# Xadow-GPS-v2.net
KiCad netlist of a schematic drawn in EAGLE
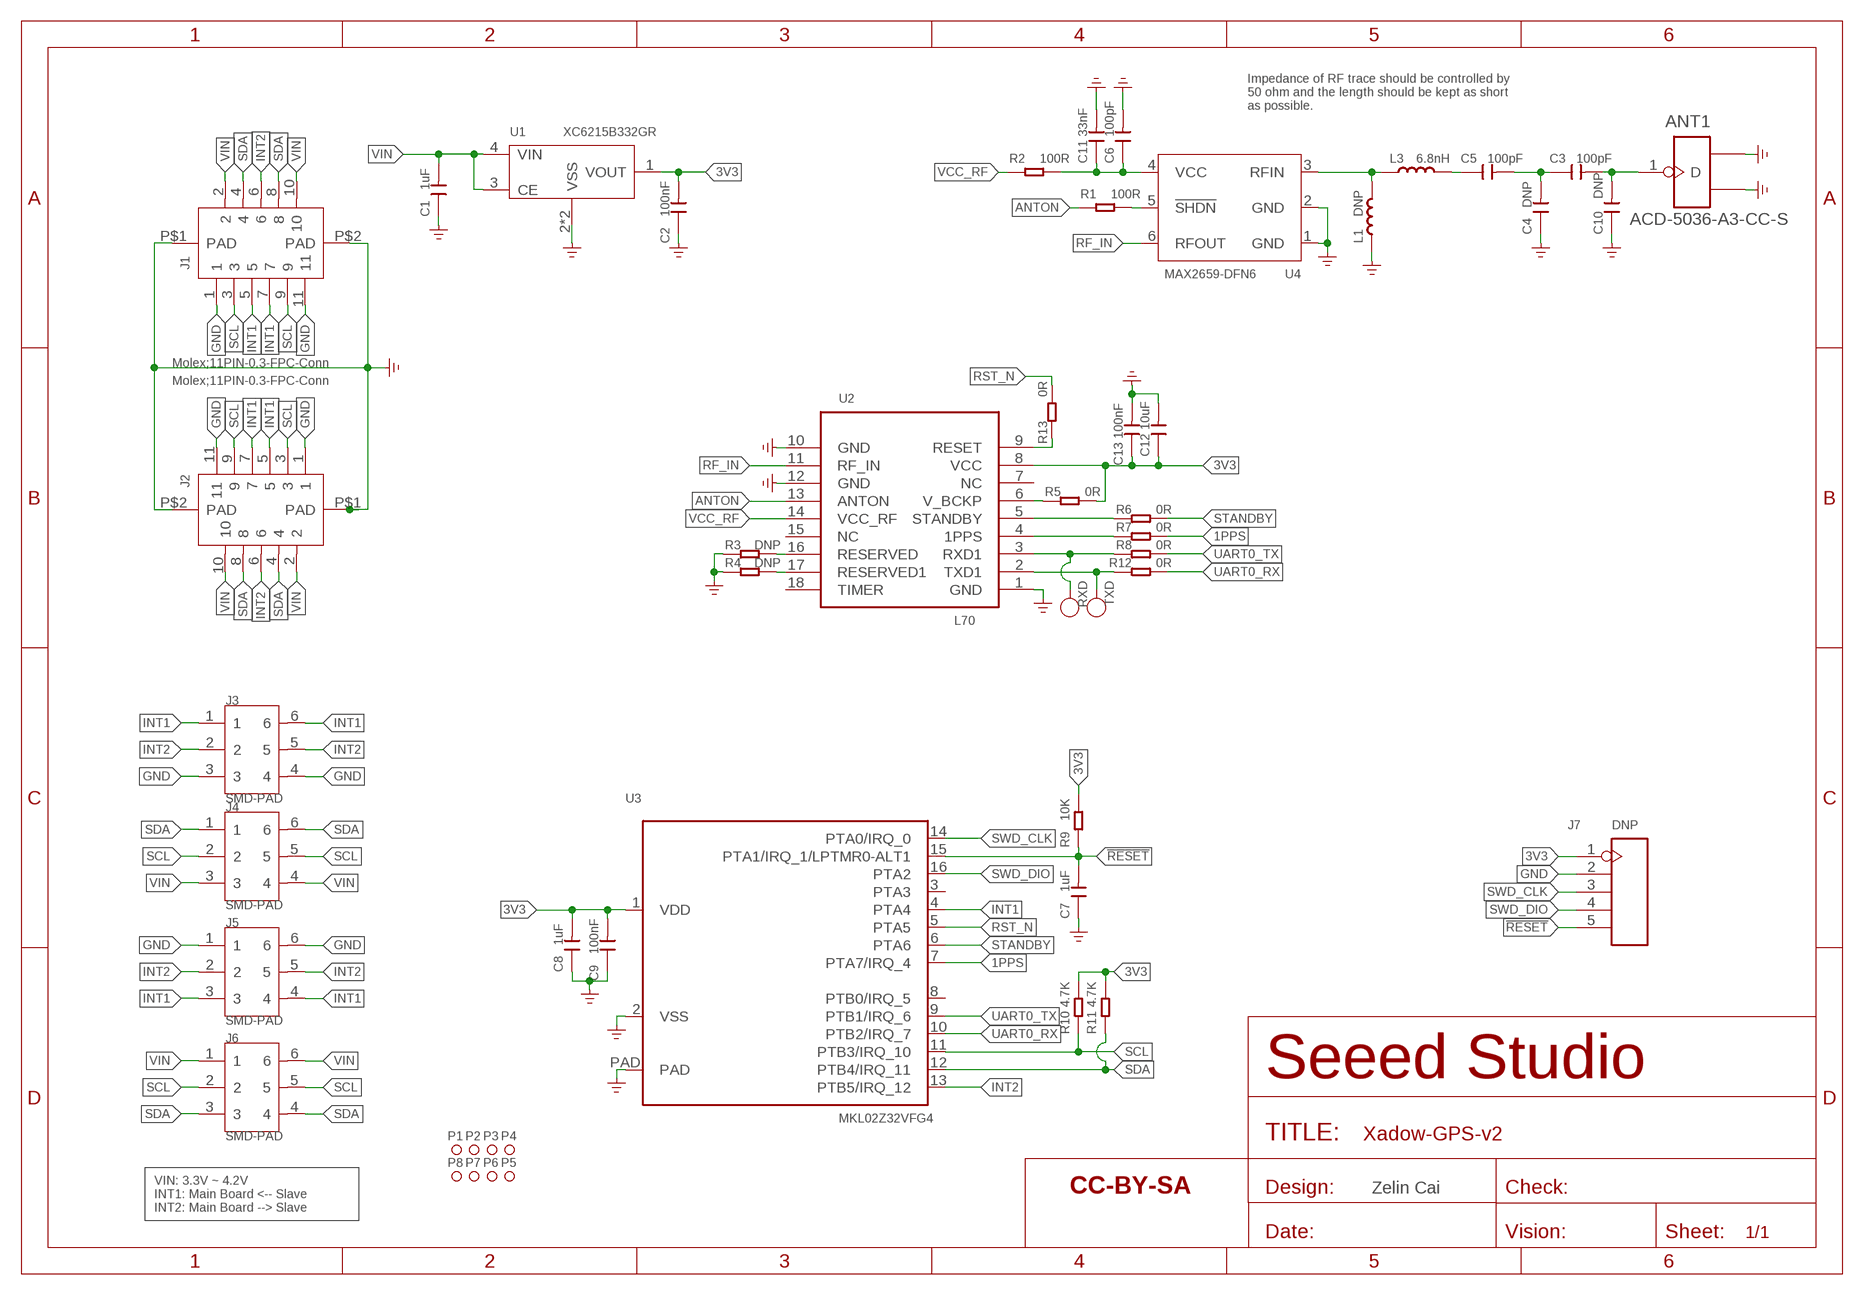
[diagram p0: schematic, sheet 1]

(export (version "E")
  (design (tool "Eeschema 10.0.6"))
  (components
    (comp (ref "ANT1")
      (value "ACD-5036-A3-CC-S")
      (footprint "eagle-import:ANT3-SMD-5.2X3.7X0.7MM")
      (libsource (lib "eagle-import") (part "ANTENNA-ACD5036"))
    )
    (comp (ref "C1")
      (value "1uF")
      (footprint "eagle-import:C0402")
      (libsource (lib "eagle-import") (part "CAP-0402"))
    )
    (comp (ref "C2")
      (value "100nF")
      (footprint "eagle-import:C0201")
      (libsource (lib "eagle-import") (part "CAP-0201"))
    )
    (comp (ref "C3")
      (value "100pF")
      (footprint "eagle-import:C0201")
      (libsource (lib "eagle-import") (part "CAP-0201"))
    )
    (comp (ref "C4")
      (value "DNP")
      (footprint "eagle-import:C0201")
      (libsource (lib "eagle-import") (part "CAP-0201"))
    )
    (comp (ref "C5")
      (value "100pF")
      (footprint "eagle-import:C0201")
      (libsource (lib "eagle-import") (part "CAP-0201"))
    )
    (comp (ref "C6")
      (value "100pF")
      (footprint "eagle-import:C0201")
      (libsource (lib "eagle-import") (part "CAP-0201"))
    )
    (comp (ref "C7")
      (value "1uF")
      (footprint "eagle-import:C0201")
      (libsource (lib "eagle-import") (part "CAP-0201"))
    )
    (comp (ref "C8")
      (value "1uF")
      (footprint "eagle-import:C0402")
      (libsource (lib "eagle-import") (part "CAP-0402"))
    )
    (comp (ref "C9")
      (value "100nF")
      (footprint "eagle-import:C0201")
      (libsource (lib "eagle-import") (part "CAP-0201"))
    )
    (comp (ref "C10")
      (value "DNP")
      (footprint "eagle-import:C0201")
      (libsource (lib "eagle-import") (part "CAP-0201"))
    )
    (comp (ref "C11")
      (value "33nF")
      (footprint "eagle-import:C0201")
      (libsource (lib "eagle-import") (part "CAP-0201"))
    )
    (comp (ref "C12")
      (value "10uF")
      (footprint "eagle-import:C0402")
      (libsource (lib "eagle-import") (part "CAP-0402"))
    )
    (comp (ref "C13")
      (value "100nF")
      (footprint "eagle-import:C0201")
      (libsource (lib "eagle-import") (part "CAP-0201"))
    )
    (comp (ref "FR")
      (value "PAGE1")
      (footprint "eagle-import:SEEEDSTUDIO-PCB-FRAME")
      (libsource (lib "eagle-import") (part "SEEEDSTUDIO-OPEN-SCH-FRAME"))
    )
    (comp (ref "J1")
      (value "Molex;11PIN-0.3-FPC-Conn")
      (footprint "eagle-import:FPC11-SMD-0.3(FH35C)")
      (libsource (lib "eagle-import") (part "FPC-CONNECTER-11P(FH35C-11S-0.3SHW(50))"))
    )
    (comp (ref "J2")
      (value "Molex;11PIN-0.3-FPC-Conn")
      (footprint "eagle-import:FPC11-SMD-0.3(FH35C)")
      (libsource (lib "eagle-import") (part "FPC-CONNECTER-11P(FH35C-11S-0.3SHW(50))"))
    )
    (comp (ref "J3")
      (value "SMD-PAD")
      (footprint "eagle-import:6P-DIP-2_ROUND")
      (libsource (lib "eagle-import") (part "HEADER6_ROUND"))
    )
    (comp (ref "J4")
      (value "SMD-PAD")
      (footprint "eagle-import:6P-DIP-2")
      (libsource (lib "eagle-import") (part "HEADER6"))
    )
    (comp (ref "J5")
      (value "SMD-PAD")
      (footprint "eagle-import:6P-DIP-2_ROUND")
      (libsource (lib "eagle-import") (part "HEADER6_ROUND"))
    )
    (comp (ref "J6")
      (value "SMD-PAD")
      (footprint "eagle-import:6P-DIP-2_S3")
      (libsource (lib "eagle-import") (part "HEADER6_S3"))
    )
    (comp (ref "J7")
      (value "DNP")
      (footprint "eagle-import:H5-SMD-2.0-TEST")
      (libsource (lib "eagle-import") (part "HEADER-5P'TEST'"))
    )
    (comp (ref "L1")
      (value "DNP")
      (footprint "eagle-import:L0201")
      (libsource (lib "eagle-import") (part "INDUCTOR/FERRITE-BEAD-0201"))
    )
    (comp (ref "L3")
      (value "6.8nH")
      (footprint "eagle-import:L0201")
      (libsource (lib "eagle-import") (part "INDUCTOR/FERRITE-BEAD-0201"))
    )
    (comp (ref "P1")
      (value "MRK")
      (footprint "eagle-import:ROUND-MARK-1.0")
      (fields (field (name "PARTNO") "DNP"))
      (libsource (lib "eagle-import") (part "MARK-1.0'ANNULAR'"))
    )
    (comp (ref "P2")
      (value "MRK")
      (footprint "eagle-import:ROUND-MARK-1.0")
      (fields (field (name "PARTNO") "DNP"))
      (libsource (lib "eagle-import") (part "MARK-1.0'ANNULAR'"))
    )
    (comp (ref "P3")
      (value "MRK")
      (footprint "eagle-import:ROUND-MARK-1.0")
      (fields (field (name "PARTNO") "DNP"))
      (libsource (lib "eagle-import") (part "MARK-1.0'ANNULAR'"))
    )
    (comp (ref "P4")
      (value "MRK")
      (footprint "eagle-import:ROUND-MARK-1.0")
      (fields (field (name "PARTNO") "DNP"))
      (libsource (lib "eagle-import") (part "MARK-1.0'ANNULAR'"))
    )
    (comp (ref "P5")
      (value "MRK")
      (footprint "eagle-import:ROUND-MARK-1.0")
      (fields (field (name "PARTNO") "DNP"))
      (libsource (lib "eagle-import") (part "MARK-1.0'ANNULAR'"))
    )
    (comp (ref "P6")
      (value "MRK")
      (footprint "eagle-import:ROUND-MARK-1.0")
      (fields (field (name "PARTNO") "DNP"))
      (libsource (lib "eagle-import") (part "MARK-1.0'ANNULAR'"))
    )
    (comp (ref "P7")
      (value "MRK")
      (footprint "eagle-import:ROUND-MARK-1.0")
      (fields (field (name "PARTNO") "DNP"))
      (libsource (lib "eagle-import") (part "MARK-1.0'ANNULAR'"))
    )
    (comp (ref "P8")
      (value "MRK")
      (footprint "eagle-import:ROUND-MARK-1.0")
      (fields (field (name "PARTNO") "DNP"))
      (libsource (lib "eagle-import") (part "MARK-1.0'ANNULAR'"))
    )
    (comp (ref "R1")
      (value "100R")
      (footprint "eagle-import:R0201")
      (libsource (lib "eagle-import") (part "RES-0201"))
    )
    (comp (ref "R2")
      (value "100R")
      (footprint "eagle-import:R0201")
      (libsource (lib "eagle-import") (part "RES-0201"))
    )
    (comp (ref "R3")
      (value "DNP")
      (footprint "eagle-import:R0201")
      (libsource (lib "eagle-import") (part "RES-0201"))
    )
    (comp (ref "R4")
      (value "DNP")
      (footprint "eagle-import:R0201")
      (libsource (lib "eagle-import") (part "RES-0201"))
    )
    (comp (ref "R5")
      (value "0R")
      (footprint "eagle-import:R0201")
      (libsource (lib "eagle-import") (part "RES-0201"))
    )
    (comp (ref "R6")
      (value "0R")
      (footprint "eagle-import:R0201")
      (libsource (lib "eagle-import") (part "RES-0201"))
    )
    (comp (ref "R7")
      (value "0R")
      (footprint "eagle-import:R0201")
      (libsource (lib "eagle-import") (part "RES-0201"))
    )
    (comp (ref "R8")
      (value "0R")
      (footprint "eagle-import:R0201")
      (libsource (lib "eagle-import") (part "RES-0201"))
    )
    (comp (ref "R9")
      (value "10K")
      (footprint "eagle-import:R0201")
      (libsource (lib "eagle-import") (part "RES-0201"))
    )
    (comp (ref "R10")
      (value "4.7K")
      (footprint "eagle-import:R0201")
      (libsource (lib "eagle-import") (part "RES-0201"))
    )
    (comp (ref "R11")
      (value "4.7K")
      (footprint "eagle-import:R0201")
      (libsource (lib "eagle-import") (part "RES-0201"))
    )
    (comp (ref "R12")
      (value "0R")
      (footprint "eagle-import:R0201")
      (libsource (lib "eagle-import") (part "RES-0201"))
    )
    (comp (ref "R13")
      (value "0R")
      (footprint "eagle-import:R0201")
      (libsource (lib "eagle-import") (part "RES-0201"))
    )
    (comp (ref "RXD")
      (value "RXD")
      (footprint "eagle-import:TP-D45MIL")
      (fields (field (name "PARTNO") "DNP"))
      (libsource (lib "eagle-import") (part "TEST-POINT'4545'"))
    )
    (comp (ref "TXD")
      (value "TXD")
      (footprint "eagle-import:TP-D45MIL")
      (fields (field (name "PARTNO") "DNP"))
      (libsource (lib "eagle-import") (part "TEST-POINT'4545'"))
    )
    (comp (ref "U1")
      (value "XC6215B332GR")
      (footprint "eagle-import:USP4-0.6-1.2X1.6MM")
      (libsource (lib "eagle-import") (part "PMIC-XC6215-3V3"))
    )
    (comp (ref "U2")
      (value "L70")
      (footprint "eagle-import:LGA18-1.1-9.7X10.1X2.5MM")
      (libsource (lib "eagle-import") (part "MOUDLE-GPS-L70-HARDWARE"))
    )
    (comp (ref "U3")
      (value "MKL02Z32VFG4")
      (footprint "eagle-import:QFN16G-0.5-3X3MM")
      (fields (field (name "MPN") "MKL02ZxxVFG4"))
      (libsource (lib "eagle-import") (part "CONTROLLER-MKL02ZXXVFG4"))
    )
    (comp (ref "U4")
      (value "MAX2659-DFN6")
      (footprint "eagle-import:DFN6-0.5-1.5X1.2X0.72MM")
      (fields (field (name "MPN") "MAX2659"))
      (libsource (lib "eagle-import") (part "AMPLIFIER-MAX2659"))
    )
  )
  (nets
    (net (code "1") (name "/~{RESET}") (class "Default")
      (node (ref "C7") (pin "2") (pinfunction "2_2") (pintype "passive"))
      (node (ref "J7") (pin "5") (pinfunction "5_5") (pintype "bidirectional"))
      (node (ref "R9") (pin "1") (pinfunction "1_1") (pintype "passive"))
      (node (ref "U3") (pin "15") (pinfunction "PTA1/IRQ_1/LPTMR0-ALT1_15") (pintype "bidirectional"))
    )
    (net (code "2") (name "1PPS") (class "Default")
      (node (ref "R7") (pin "1") (pinfunction "1_1") (pintype "passive"))
      (node (ref "U3") (pin "7") (pinfunction "PTA7/IRQ_4_7") (pintype "bidirectional"))
    )
    (net (code "3") (name "3V3") (class "Default")
      (node (ref "C12") (pin "1") (pinfunction "1_1") (pintype "passive"))
      (node (ref "C13") (pin "1") (pinfunction "1_1") (pintype "passive"))
      (node (ref "C2") (pin "2") (pinfunction "2_2") (pintype "passive"))
      (node (ref "C8") (pin "2") (pinfunction "2_2") (pintype "passive"))
      (node (ref "C9") (pin "2") (pinfunction "2_2") (pintype "passive"))
      (node (ref "J7") (pin "1") (pinfunction "1_1") (pintype "bidirectional"))
      (node (ref "R10") (pin "2") (pinfunction "2_2") (pintype "passive"))
      (node (ref "R11") (pin "2") (pinfunction "2_2") (pintype "passive"))
      (node (ref "R5") (pin "1") (pinfunction "1_1") (pintype "passive"))
      (node (ref "R9") (pin "2") (pinfunction "2_2") (pintype "passive"))
      (node (ref "U1") (pin "1") (pinfunction "VOUT_1") (pintype "bidirectional"))
      (node (ref "U2") (pin "8") (pinfunction "VCC_8") (pintype "power_in"))
      (node (ref "U3") (pin "1") (pinfunction "VDD_1") (pintype "power_in"))
    )
    (net (code "4") (name "ANTON") (class "Default")
      (node (ref "R1") (pin "2") (pinfunction "2_2") (pintype "passive"))
      (node (ref "U2") (pin "13") (pinfunction "ANTON_13") (pintype "bidirectional"))
    )
    (net (code "5") (name "GND") (class "Default")
      (node (ref "ANT1") (pin "2") (pinfunction "GND1_2") (pintype "bidirectional"))
      (node (ref "ANT1") (pin "3") (pinfunction "GND2_3") (pintype "bidirectional"))
      (node (ref "C1") (pin "1") (pinfunction "1_1") (pintype "passive"))
      (node (ref "C10") (pin "1") (pinfunction "1_1") (pintype "passive"))
      (node (ref "C11") (pin "2") (pinfunction "2_2") (pintype "passive"))
      (node (ref "C12") (pin "2") (pinfunction "2_2") (pintype "passive"))
      (node (ref "C13") (pin "2") (pinfunction "2_2") (pintype "passive"))
      (node (ref "C2") (pin "1") (pinfunction "1_1") (pintype "passive"))
      (node (ref "C4") (pin "1") (pinfunction "1_1") (pintype "passive"))
      (node (ref "C6") (pin "2") (pinfunction "2_2") (pintype "passive"))
      (node (ref "C7") (pin "1") (pinfunction "1_1") (pintype "passive"))
      (node (ref "C8") (pin "1") (pinfunction "1_1") (pintype "passive"))
      (node (ref "C9") (pin "1") (pinfunction "1_1") (pintype "passive"))
      (node (ref "J1") (pin "1") (pinfunction "1_1") (pintype "bidirectional"))
      (node (ref "J1") (pin "11") (pinfunction "11_11") (pintype "bidirectional"))
      (node (ref "J1") (pin "P$1") (pinfunction "PAD_P$1") (pintype "bidirectional"))
      (node (ref "J1") (pin "P$2") (pinfunction "PAD_P$2") (pintype "bidirectional"))
      (node (ref "J2") (pin "1") (pinfunction "1_1") (pintype "bidirectional"))
      (node (ref "J2") (pin "11") (pinfunction "11_11") (pintype "bidirectional"))
      (node (ref "J2") (pin "P$1") (pinfunction "PAD_P$1") (pintype "bidirectional"))
      (node (ref "J2") (pin "P$2") (pinfunction "PAD_P$2") (pintype "bidirectional"))
      (node (ref "J3") (pin "3") (pinfunction "3_3") (pintype "bidirectional"))
      (node (ref "J3") (pin "4") (pinfunction "4_4") (pintype "bidirectional"))
      (node (ref "J5") (pin "1") (pinfunction "1_1") (pintype "bidirectional"))
      (node (ref "J5") (pin "6") (pinfunction "6_6") (pintype "bidirectional"))
      (node (ref "J7") (pin "2") (pinfunction "2_2") (pintype "bidirectional"))
      (node (ref "L1") (pin "1") (pinfunction "1_1") (pintype "passive"))
      (node (ref "R3") (pin "2") (pinfunction "2_2") (pintype "passive"))
      (node (ref "R4") (pin "2") (pinfunction "2_2") (pintype "passive"))
      (node (ref "U1") (pin "2") (pinfunction "VSS_2") (pintype "bidirectional"))
      (node (ref "U1") (pin "PAD") (pinfunction "VSS_PAD") (pintype "bidirectional"))
      (node (ref "U2") (pin "1") (pinfunction "GND_1") (pintype "power_in"))
      (node (ref "U2") (pin "10") (pinfunction "GND_10") (pintype "power_in"))
      (node (ref "U2") (pin "12") (pinfunction "GND_12") (pintype "bidirectional"))
      (node (ref "U3") (pin "2") (pinfunction "VSS_2") (pintype "power_in"))
      (node (ref "U3") (pin "PAD") (pinfunction "PAD_PAD") (pintype "power_in"))
      (node (ref "U4") (pin "1") (pinfunction "GND_1") (pintype "power_in"))
      (node (ref "U4") (pin "2") (pinfunction "GND_2") (pintype "power_in"))
    )
    (net (code "6") (name "INT1") (class "Default")
      (node (ref "J1") (pin "5") (pinfunction "5_5") (pintype "bidirectional"))
      (node (ref "J1") (pin "7") (pinfunction "7_7") (pintype "bidirectional"))
      (node (ref "J2") (pin "5") (pinfunction "5_5") (pintype "bidirectional"))
      (node (ref "J2") (pin "7") (pinfunction "7_7") (pintype "bidirectional"))
      (node (ref "J3") (pin "1") (pinfunction "1_1") (pintype "bidirectional"))
      (node (ref "J3") (pin "6") (pinfunction "6_6") (pintype "bidirectional"))
      (node (ref "J5") (pin "3") (pinfunction "3_3") (pintype "bidirectional"))
      (node (ref "J5") (pin "4") (pinfunction "4_4") (pintype "bidirectional"))
      (node (ref "U3") (pin "4") (pinfunction "PTA4_4") (pintype "bidirectional"))
    )
    (net (code "7") (name "INT2") (class "Default")
      (node (ref "J1") (pin "6") (pinfunction "6_6") (pintype "bidirectional"))
      (node (ref "J2") (pin "6") (pinfunction "6_6") (pintype "bidirectional"))
      (node (ref "J3") (pin "2") (pinfunction "2_2") (pintype "bidirectional"))
      (node (ref "J3") (pin "5") (pinfunction "5_5") (pintype "bidirectional"))
      (node (ref "J5") (pin "2") (pinfunction "2_2") (pintype "bidirectional"))
      (node (ref "J5") (pin "5") (pinfunction "5_5") (pintype "bidirectional"))
      (node (ref "U3") (pin "13") (pinfunction "PTB5/IRQ_12_13") (pintype "bidirectional"))
    )
    (net (code "8") (name "Net-(ANT1-D)") (class "Default")
      (node (ref "ANT1") (pin "1") (pinfunction "D_1") (pintype "bidirectional"))
      (node (ref "C10") (pin "2") (pinfunction "2_2") (pintype "passive"))
      (node (ref "C3") (pin "2") (pinfunction "2_2") (pintype "passive"))
    )
    (net (code "9") (name "Net-(C3-Pad1)") (class "Default")
      (node (ref "C3") (pin "1") (pinfunction "1_1") (pintype "passive"))
      (node (ref "C4") (pin "2") (pinfunction "2_2") (pintype "passive"))
      (node (ref "C5") (pin "2") (pinfunction "2_2") (pintype "passive"))
    )
    (net (code "10") (name "Net-(C5-Pad1)") (class "Default")
      (node (ref "C5") (pin "1") (pinfunction "1_1") (pintype "passive"))
      (node (ref "L3") (pin "2") (pinfunction "2_2") (pintype "passive"))
    )
    (net (code "11") (name "Net-(U2-1PPS)") (class "Default")
      (node (ref "R7") (pin "2") (pinfunction "2_2") (pintype "passive"))
      (node (ref "U2") (pin "4") (pinfunction "1PPS_4") (pintype "bidirectional"))
    )
    (net (code "12") (name "Net-(U2-RESERVED)") (class "Default")
      (node (ref "R3") (pin "1") (pinfunction "1_1") (pintype "passive"))
      (node (ref "U2") (pin "16") (pinfunction "RESERVED_16") (pintype "bidirectional"))
    )
    (net (code "13") (name "Net-(U2-RESERVED1)") (class "Default")
      (node (ref "R4") (pin "1") (pinfunction "1_1") (pintype "passive"))
      (node (ref "U2") (pin "17") (pinfunction "RESERVED1_17") (pintype "bidirectional"))
    )
    (net (code "14") (name "Net-(U2-RESET)") (class "Default")
      (node (ref "R13") (pin "2") (pinfunction "2_2") (pintype "passive"))
      (node (ref "U2") (pin "9") (pinfunction "RESET_9") (pintype "bidirectional"))
    )
    (net (code "15") (name "Net-(U2-RXD1)") (class "Default")
      (node (ref "R8") (pin "2") (pinfunction "2_2") (pintype "passive"))
      (node (ref "RXD") (pin "T") (pinfunction "T_T") (pintype "bidirectional"))
      (node (ref "U2") (pin "3") (pinfunction "RXD1_3") (pintype "bidirectional"))
    )
    (net (code "16") (name "Net-(U2-STANDBY)") (class "Default")
      (node (ref "R6") (pin "2") (pinfunction "2_2") (pintype "passive"))
      (node (ref "U2") (pin "5") (pinfunction "STANDBY_5") (pintype "bidirectional"))
    )
    (net (code "17") (name "Net-(U2-TXD1)") (class "Default")
      (node (ref "R12") (pin "2") (pinfunction "2_2") (pintype "passive"))
      (node (ref "TXD") (pin "T") (pinfunction "T_T") (pintype "bidirectional"))
      (node (ref "U2") (pin "2") (pinfunction "TXD1_2") (pintype "bidirectional"))
    )
    (net (code "18") (name "Net-(U2-V_BCKP)") (class "Default")
      (node (ref "R5") (pin "2") (pinfunction "2_2") (pintype "passive"))
      (node (ref "U2") (pin "6") (pinfunction "V_BCKP_6") (pintype "bidirectional"))
    )
    (net (code "19") (name "Net-(U4-RFIN)") (class "Default")
      (node (ref "L1") (pin "2") (pinfunction "2_2") (pintype "passive"))
      (node (ref "L3") (pin "1") (pinfunction "1_1") (pintype "passive"))
      (node (ref "U4") (pin "3") (pinfunction "RFIN_3") (pintype "bidirectional"))
    )
    (net (code "20") (name "Net-(U4-VCC)") (class "Default")
      (node (ref "C11") (pin "1") (pinfunction "1_1") (pintype "passive"))
      (node (ref "C6") (pin "1") (pinfunction "1_1") (pintype "passive"))
      (node (ref "R2") (pin "1") (pinfunction "1_1") (pintype "passive"))
      (node (ref "U4") (pin "4") (pinfunction "VCC_4") (pintype "power_in"))
    )
    (net (code "21") (name "Net-(U4-~{SHDN})") (class "Default")
      (node (ref "R1") (pin "1") (pinfunction "1_1") (pintype "passive"))
      (node (ref "U4") (pin "5") (pinfunction "~{SHDN}_5") (pintype "bidirectional"))
    )
    (net (code "22") (name "RF_IN") (class "Default")
      (node (ref "U2") (pin "11") (pinfunction "RF_IN_11") (pintype "bidirectional"))
      (node (ref "U4") (pin "6") (pinfunction "RFOUT_6") (pintype "bidirectional"))
    )
    (net (code "23") (name "RST_N") (class "Default")
      (node (ref "R13") (pin "1") (pinfunction "1_1") (pintype "passive"))
      (node (ref "U3") (pin "5") (pinfunction "PTA5_5") (pintype "bidirectional"))
    )
    (net (code "24") (name "SCL") (class "Default")
      (node (ref "J1") (pin "3") (pinfunction "3_3") (pintype "bidirectional"))
      (node (ref "J1") (pin "9") (pinfunction "9_9") (pintype "bidirectional"))
      (node (ref "J2") (pin "3") (pinfunction "3_3") (pintype "bidirectional"))
      (node (ref "J2") (pin "9") (pinfunction "9_9") (pintype "bidirectional"))
      (node (ref "J4") (pin "2") (pinfunction "2_2") (pintype "bidirectional"))
      (node (ref "J4") (pin "5") (pinfunction "5_5") (pintype "bidirectional"))
      (node (ref "J6") (pin "2") (pinfunction "2_2") (pintype "bidirectional"))
      (node (ref "J6") (pin "5") (pinfunction "5_5") (pintype "bidirectional"))
      (node (ref "R10") (pin "1") (pinfunction "1_1") (pintype "passive"))
      (node (ref "U3") (pin "11") (pinfunction "PTB3/IRQ_10_11") (pintype "bidirectional"))
    )
    (net (code "25") (name "SDA") (class "Default")
      (node (ref "J1") (pin "4") (pinfunction "4_4") (pintype "bidirectional"))
      (node (ref "J1") (pin "8") (pinfunction "8_8") (pintype "bidirectional"))
      (node (ref "J2") (pin "4") (pinfunction "4_4") (pintype "bidirectional"))
      (node (ref "J2") (pin "8") (pinfunction "8_8") (pintype "bidirectional"))
      (node (ref "J4") (pin "1") (pinfunction "1_1") (pintype "bidirectional"))
      (node (ref "J4") (pin "6") (pinfunction "6_6") (pintype "bidirectional"))
      (node (ref "J6") (pin "3") (pinfunction "3_3") (pintype "bidirectional"))
      (node (ref "J6") (pin "4") (pinfunction "4_4") (pintype "bidirectional"))
      (node (ref "R11") (pin "1") (pinfunction "1_1") (pintype "passive"))
      (node (ref "U3") (pin "12") (pinfunction "PTB4/IRQ_11_12") (pintype "bidirectional"))
    )
    (net (code "26") (name "STANDBY") (class "Default")
      (node (ref "R6") (pin "1") (pinfunction "1_1") (pintype "passive"))
      (node (ref "U3") (pin "6") (pinfunction "PTA6_6") (pintype "bidirectional"))
    )
    (net (code "27") (name "SWD_CLK") (class "Default")
      (node (ref "J7") (pin "3") (pinfunction "3_3") (pintype "bidirectional"))
      (node (ref "U3") (pin "14") (pinfunction "PTA0/IRQ_0_14") (pintype "bidirectional"))
    )
    (net (code "28") (name "SWD_DIO") (class "Default")
      (node (ref "J7") (pin "4") (pinfunction "4_4") (pintype "bidirectional"))
      (node (ref "U3") (pin "16") (pinfunction "PTA2_16") (pintype "bidirectional"))
    )
    (net (code "29") (name "UART0_RX") (class "Default")
      (node (ref "R12") (pin "1") (pinfunction "1_1") (pintype "passive"))
      (node (ref "U3") (pin "10") (pinfunction "PTB2/IRQ_7_10") (pintype "bidirectional"))
    )
    (net (code "30") (name "UART0_TX") (class "Default")
      (node (ref "R8") (pin "1") (pinfunction "1_1") (pintype "passive"))
      (node (ref "U3") (pin "9") (pinfunction "PTB1/IRQ_6_9") (pintype "bidirectional"))
    )
    (net (code "31") (name "VCC_RF") (class "Default")
      (node (ref "R2") (pin "2") (pinfunction "2_2") (pintype "passive"))
      (node (ref "U2") (pin "14") (pinfunction "VCC_RF_14") (pintype "power_in"))
    )
    (net (code "32") (name "VIN") (class "Default")
      (node (ref "C1") (pin "2") (pinfunction "2_2") (pintype "passive"))
      (node (ref "J1") (pin "10") (pinfunction "10_10") (pintype "bidirectional"))
      (node (ref "J1") (pin "2") (pinfunction "2_2") (pintype "bidirectional"))
      (node (ref "J2") (pin "10") (pinfunction "10_10") (pintype "bidirectional"))
      (node (ref "J2") (pin "2") (pinfunction "2_2") (pintype "bidirectional"))
      (node (ref "J4") (pin "3") (pinfunction "3_3") (pintype "bidirectional"))
      (node (ref "J4") (pin "4") (pinfunction "4_4") (pintype "bidirectional"))
      (node (ref "J6") (pin "1") (pinfunction "1_1") (pintype "bidirectional"))
      (node (ref "J6") (pin "6") (pinfunction "6_6") (pintype "bidirectional"))
      (node (ref "U1") (pin "3") (pinfunction "CE_3") (pintype "bidirectional"))
      (node (ref "U1") (pin "4") (pinfunction "VIN_4") (pintype "bidirectional"))
    )
    (net (code "33") (name "unconnected-(U2-NC-Pad7)") (class "Default")
      (node (ref "U2") (pin "7") (pinfunction "NC_7") (pintype "bidirectional"))
    )
    (net (code "34") (name "unconnected-(U2-NC-Pad15)") (class "Default")
      (node (ref "U2") (pin "15") (pinfunction "NC_15") (pintype "bidirectional"))
    )
    (net (code "35") (name "unconnected-(U2-TIMER-Pad18)") (class "Default")
      (node (ref "U2") (pin "18") (pinfunction "TIMER_18") (pintype "bidirectional"))
    )
    (net (code "36") (name "unconnected-(U3-PTA3-Pad3)") (class "Default")
      (node (ref "U3") (pin "3") (pinfunction "PTA3_3") (pintype "bidirectional"))
    )
    (net (code "37") (name "unconnected-(U3-PTB0{slash}IRQ_5-Pad8)") (class "Default")
      (node (ref "U3") (pin "8") (pinfunction "PTB0/IRQ_5_8") (pintype "bidirectional"))
    )
  )
)
